# Power_Supply.net
KiCad netlist of a schematic drawn in Altium Designer
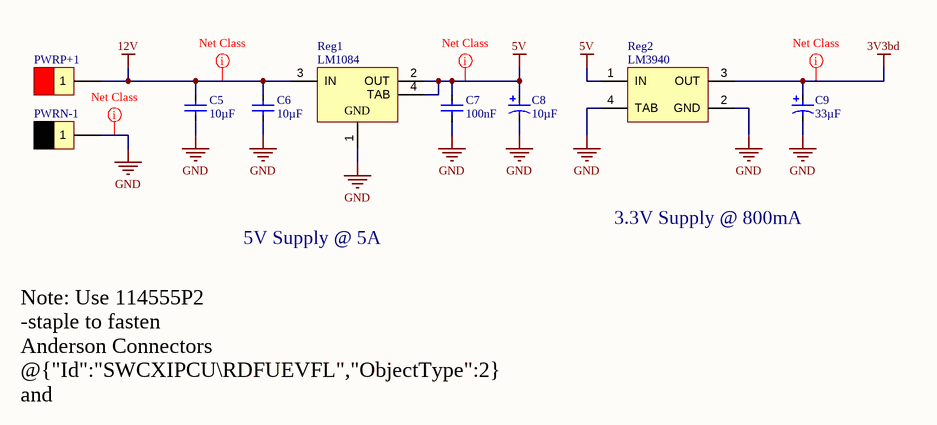
[diagram p0: Power Supply.SchDoc]

(export (version "E")
  (design (tool "Eeschema 10.0.6"))
  (components
    (comp (ref "C5")
      (value "10µF")
      (footprint "CAPC2013X135X45ML10T25")
      (fields (field (name "TOLERANCE") "10%") (field (name "Comment") "CAP_Murata"))
      (libsource (lib "Advanced] Training Course - A365") (part "CAP_Murata"))
    )
    (comp (ref "C6")
      (value "10µF")
      (footprint "CAPC2013X135X45ML10T25")
      (fields (field (name "TOLERANCE") "10%") (field (name "Comment") "CAP_Murata"))
      (libsource (lib "Advanced] Training Course - A365") (part "CAP_Murata"))
    )
    (comp (ref "C7")
      (value "100nF")
      (footprint "0603C_L")
      (fields (field (name "Comment") "Cap100nF_50V_0603"))
      (libsource (lib "Advanced] Training Course - A365") (part "CAP General"))
    )
    (comp (ref "C8")
      (value "10µF")
      (footprint "AVX-TPSB106K020R1000_L")
      (fields (field (name "Comment") "TPSB106K020R1000"))
      (libsource (lib "Advanced] Training Course - A365") (part "CAP_Polar Generic"))
    )
    (comp (ref "C9")
      (value "33µF")
      (footprint "FP-TAJY-MFG")
      (fields (field (name "Comment") "TAJY336K020RNJ"))
      (libsource (lib "Advanced] Training Course - A365") (part "CAP_Polar Generic"))
    )
    (comp (ref "PWRN-1")
      (value "Anderson-1Pin BLK_PCB_RHT")
      (footprint "Anderson_BLK_RHT_BOT")
      (description "Connector Accessory, Contact, Copper Alloy")
      (libsource (lib "Advanced] Training Course - A365") (part "Anderson-1Pin BLK_PCB_RHT"))
    )
    (comp (ref "PWRP+1")
      (value "Anderson-1Pin RED_PCB_RHT")
      (footprint "Anderson_RED_RHT_BOT")
      (description "Connector Accessory, Contact, Copper Alloy")
      (libsource (lib "TC - Altium Essentials Course A365 13") (part "Anderson-1Pin RED_PCB_RHT"))
    )
    (comp (ref "Reg1")
      (value "LM1084")
      (footprint "KTT0003B_L")
      (description "5A Low Dropout Positive Regulators, 3-pin TO-263, Pb-Free")
      (fields
        (field (name "MANUFACTURER") "Texas Instruments")
        (field (name "PARTNUMBER") "LM1084IS-5.0/NOPB")
        (field (name "AVAILABLE PREVIEW IMAGES") "2D")
      )
      (libsource (lib "Advanced] Training Course - A365") (part "LM1084"))
    )
    (comp (ref "Reg2")
      (value "LM3940")
      (footprint "SOT223")
      (description "1A Low Dropout Regulator for 5V to 3.3V Conversion, 4-pin SOT-223, Pb-Free")
      (fields
        (field (name "MANUFACTURER") "Texas Instruments")
        (field (name "MANUFACTURER PART NUMBER") "LM3940IMP-3.3/NOPB")
      )
      (libsource (lib "Advanced] Training Course - A365") (part "LM3940"))
    )
  )
  (nets
    (net (code "1") (name "3V3bd") (class "Default")
      (node (ref "C9") (pin "2") (pinfunction "2_2") (pintype "passive"))
      (node (ref "Reg2") (pin "3") (pinfunction "OUT_3") (pintype "power_in"))
    )
    (net (code "2") (name "5V") (class "Default")
      (node (ref "C7") (pin "2") (pinfunction "2_2") (pintype "passive"))
      (node (ref "C8") (pin "2") (pinfunction "2_2") (pintype "passive"))
      (node (ref "Reg1") (pin "2") (pinfunction "OUT_2") (pintype "power_in"))
      (node (ref "Reg1") (pin "4") (pinfunction "TAB_4") (pintype "power_in"))
      (node (ref "Reg2") (pin "1") (pinfunction "IN_1") (pintype "power_in"))
    )
    (net (code "3") (name "12V") (class "Default")
      (node (ref "C5") (pin "2") (pinfunction "2_2") (pintype "passive"))
      (node (ref "C6") (pin "2") (pinfunction "2_2") (pintype "passive"))
      (node (ref "PWRP+1") (pin "1") (pinfunction "1_1") (pintype "passive"))
      (node (ref "Reg1") (pin "3") (pinfunction "IN_3") (pintype "power_in"))
    )
    (net (code "4") (name "GND") (class "Default")
      (node (ref "C5") (pin "1") (pinfunction "1_1") (pintype "passive"))
      (node (ref "C6") (pin "1") (pinfunction "1_1") (pintype "passive"))
      (node (ref "C7") (pin "1") (pinfunction "1_1") (pintype "passive"))
      (node (ref "C8") (pin "1") (pinfunction "1_1") (pintype "passive"))
      (node (ref "C9") (pin "1") (pinfunction "1_1") (pintype "passive"))
      (node (ref "PWRN-1") (pin "1") (pinfunction "1_1") (pintype "passive"))
      (node (ref "Reg1") (pin "1") (pinfunction "GND_1") (pintype "power_in"))
      (node (ref "Reg2") (pin "2") (pinfunction "GND_2") (pintype "power_in"))
      (node (ref "Reg2") (pin "4") (pinfunction "TAB_4") (pintype "power_in"))
    )
  )
)
